# 8085_IO.net
KiCad netlist of a schematic drawn in EAGLE
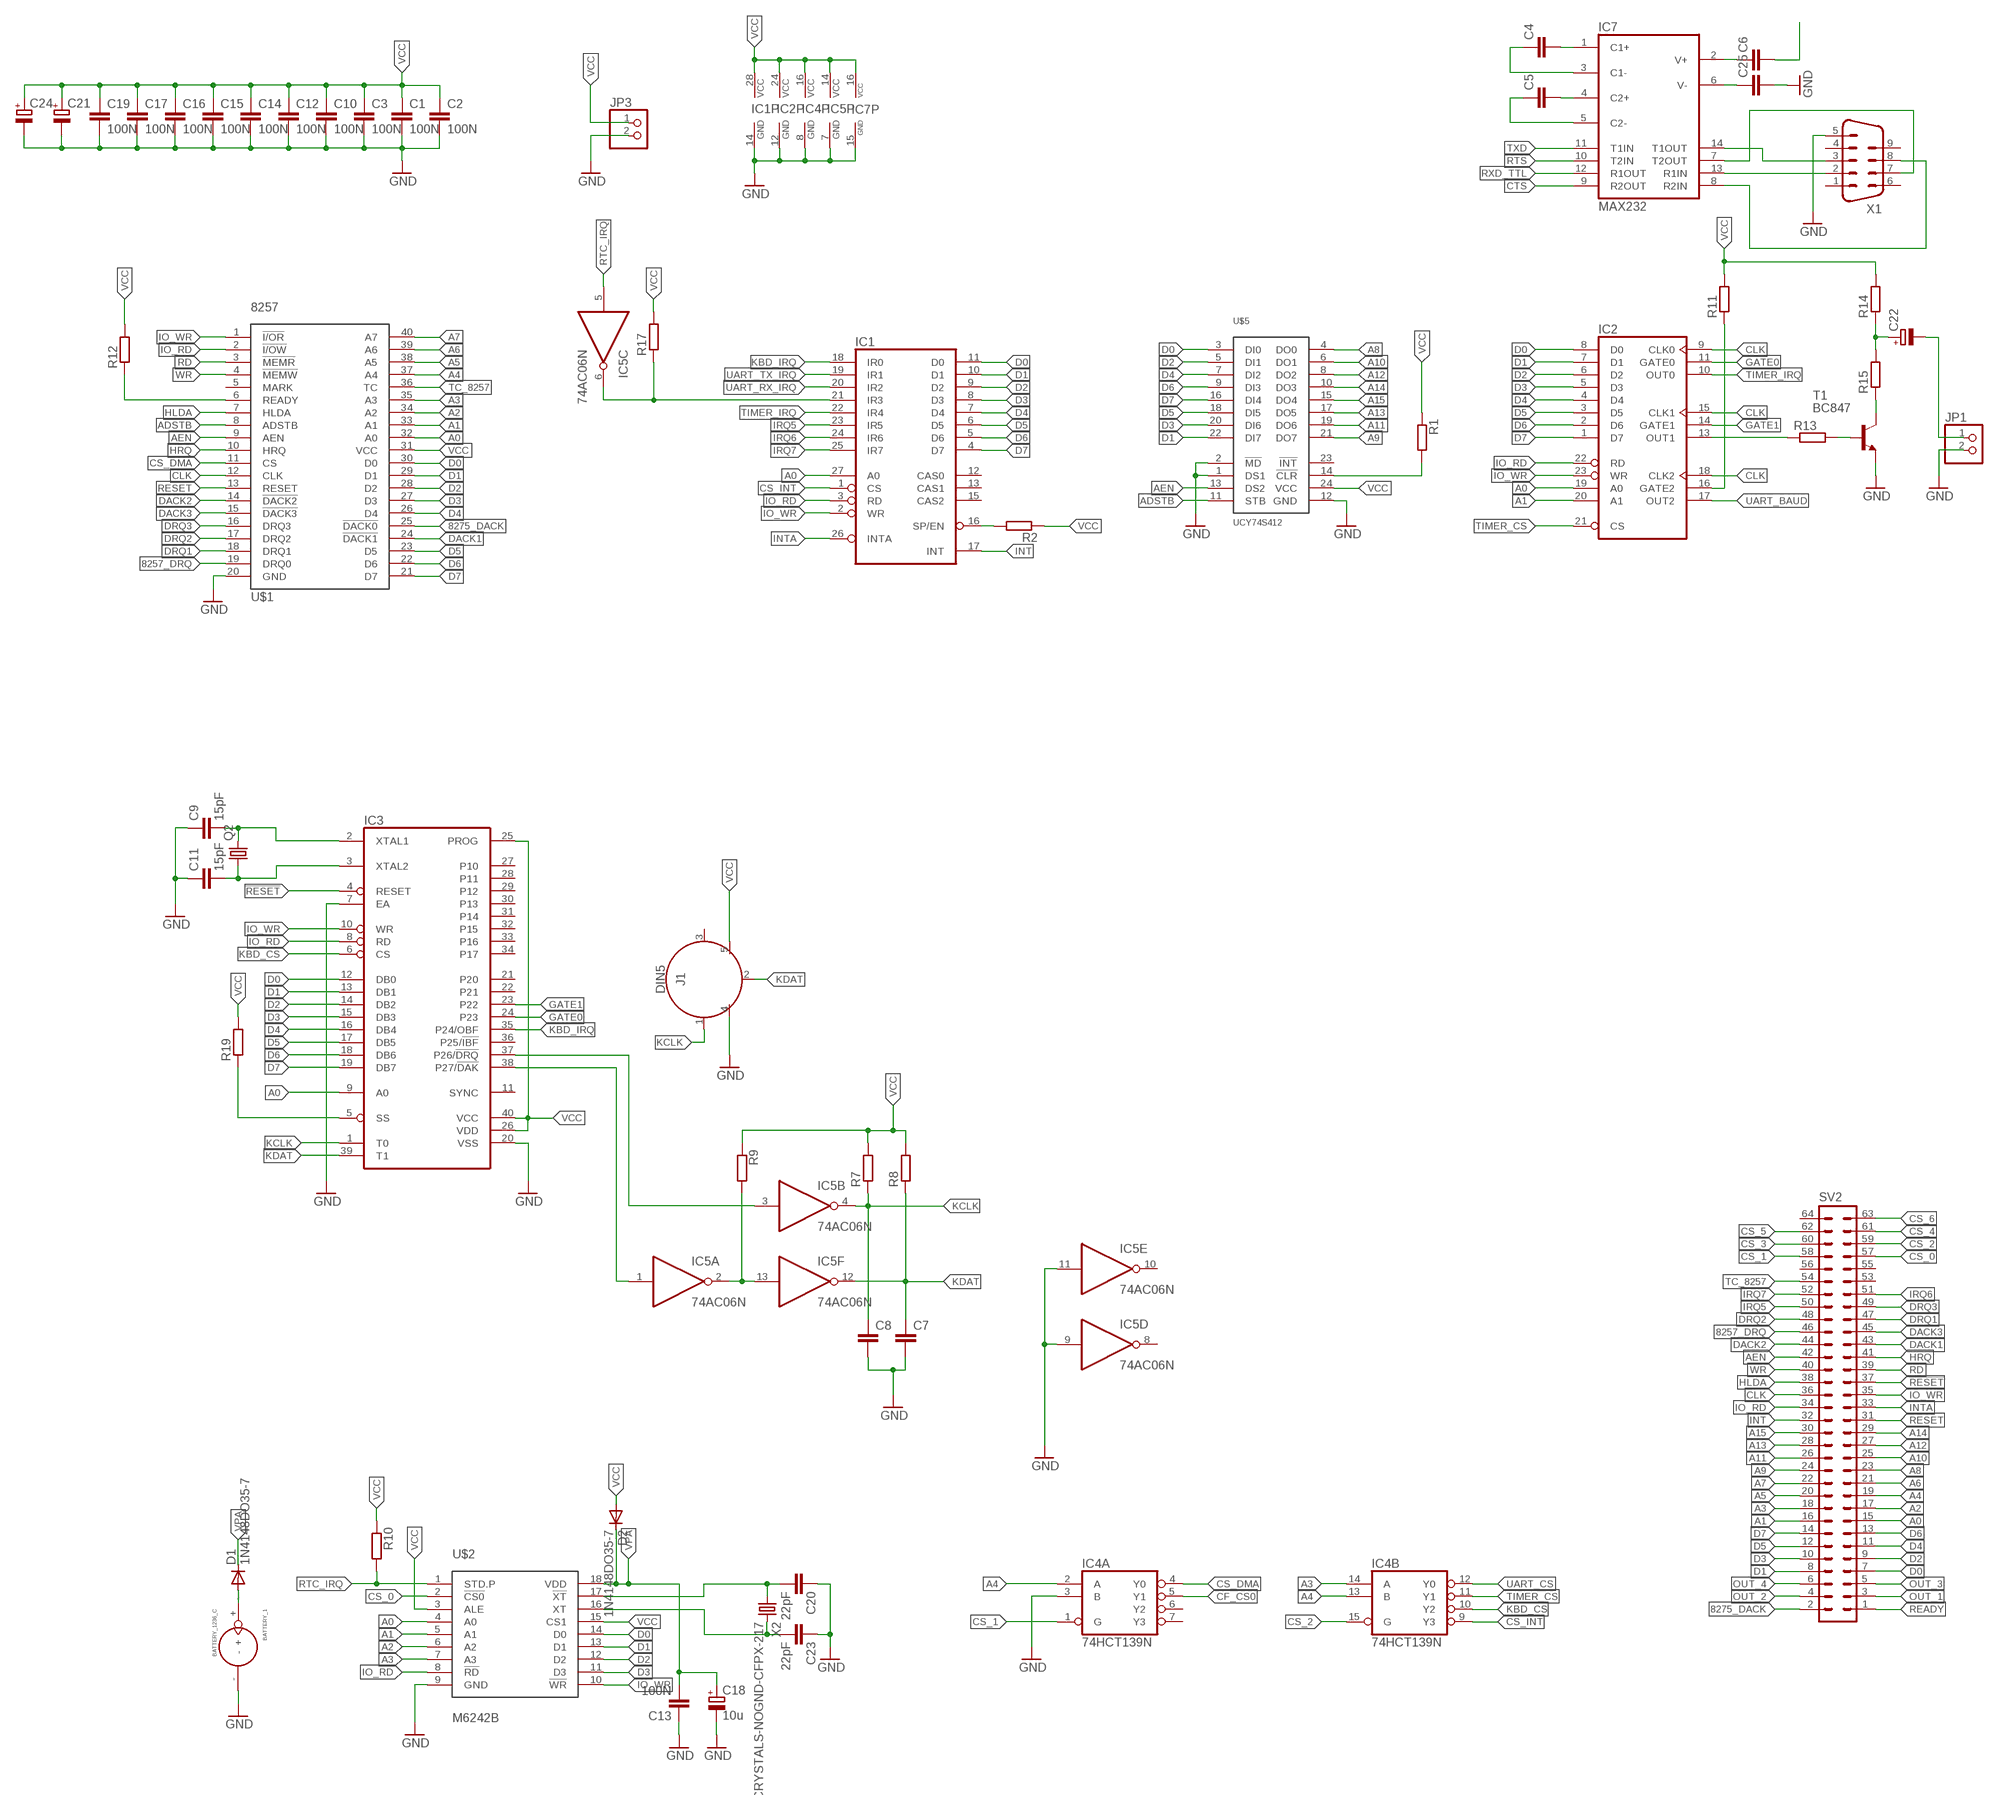
[diagram p0: schematic, sheet 1, part 1 of 2]
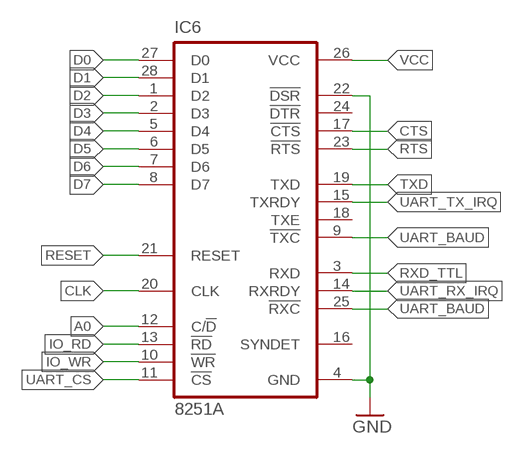
[diagram p1: schematic, sheet 1, part 2 of 2]

(export (version "E")
  (design (tool "Eeschema 10.0.6"))
  (components
    (comp (ref "BATTERY_1")
      (value "BATTERY_1236_C")
      (footprint "eagle-import:BATTERY_1236_C")
      (libsource (lib "eagle-import") (part "BATTERY_1236_C"))
    )
    (comp (ref "C1")
      (value "100N")
      (footprint "eagle-import:C0603")
      (libsource (lib "eagle-import") (part "C-EUC0603"))
    )
    (comp (ref "C2")
      (value "100N")
      (footprint "eagle-import:C1206")
      (libsource (lib "eagle-import") (part "C-EUC1206"))
    )
    (comp (ref "C3")
      (value "100N")
      (footprint "eagle-import:C0603")
      (libsource (lib "eagle-import") (part "C-EUC0603"))
    )
    (comp (ref "C4")
      (value "C-EUC0603")
      (footprint "eagle-import:C0603")
      (libsource (lib "eagle-import") (part "C-EUC0603"))
    )
    (comp (ref "C5")
      (value "C-EUC0603")
      (footprint "eagle-import:C0603")
      (libsource (lib "eagle-import") (part "C-EUC0603"))
    )
    (comp (ref "C6")
      (value "C-EUC0603")
      (footprint "eagle-import:C0603")
      (libsource (lib "eagle-import") (part "C-EUC0603"))
    )
    (comp (ref "C7")
      (value "C-EUC0603")
      (footprint "eagle-import:C0603")
      (libsource (lib "eagle-import") (part "C-EUC0603"))
    )
    (comp (ref "C8")
      (value "C-EUC0603")
      (footprint "eagle-import:C0603")
      (libsource (lib "eagle-import") (part "C-EUC0603"))
    )
    (comp (ref "C9")
      (value "15pF")
      (footprint "eagle-import:C0603")
      (libsource (lib "eagle-import") (part "C-EUC0603"))
    )
    (comp (ref "C10")
      (value "100N")
      (footprint "eagle-import:C0603")
      (libsource (lib "eagle-import") (part "C-EUC0603"))
    )
    (comp (ref "C11")
      (value "15pF")
      (footprint "eagle-import:C0603")
      (libsource (lib "eagle-import") (part "C-EUC0603"))
    )
    (comp (ref "C12")
      (value "100N")
      (footprint "eagle-import:C0603")
      (libsource (lib "eagle-import") (part "C-EUC0603"))
    )
    (comp (ref "C13")
      (value "100N")
      (footprint "eagle-import:C0603")
      (libsource (lib "eagle-import") (part "C-EUC0603"))
    )
    (comp (ref "C14")
      (value "100N")
      (footprint "eagle-import:C0603")
      (libsource (lib "eagle-import") (part "C-EUC0603"))
    )
    (comp (ref "C15")
      (value "100N")
      (footprint "eagle-import:C0603")
      (libsource (lib "eagle-import") (part "C-EUC0603"))
    )
    (comp (ref "C16")
      (value "100N")
      (footprint "eagle-import:C0603")
      (libsource (lib "eagle-import") (part "C-EUC0603"))
    )
    (comp (ref "C17")
      (value "100N")
      (footprint "eagle-import:C0603")
      (libsource (lib "eagle-import") (part "C-EUC0603"))
    )
    (comp (ref "C18")
      (value "10u")
      (footprint "eagle-import:SMC_B")
      (libsource (lib "eagle-import") (part "CPOL-EUSMCB"))
    )
    (comp (ref "C19")
      (value "100N")
      (footprint "eagle-import:C0603")
      (libsource (lib "eagle-import") (part "C-EUC0603"))
    )
    (comp (ref "C20")
      (value "22pF")
      (footprint "eagle-import:C0603")
      (libsource (lib "eagle-import") (part "C-EUC0603"))
    )
    (comp (ref "C21")
      (value "CPOL-EUE3.5-8")
      (footprint "eagle-import:E3,5-8")
      (libsource (lib "eagle-import") (part "CPOL-EUE3.5-8"))
    )
    (comp (ref "C22")
      (value "CPOL-EUE2-4")
      (footprint "eagle-import:E2-4")
      (libsource (lib "eagle-import") (part "CPOL-EUE2-4"))
    )
    (comp (ref "C23")
      (value "22pF")
      (footprint "eagle-import:C0603")
      (libsource (lib "eagle-import") (part "C-EUC0603"))
    )
    (comp (ref "C24")
      (value "CPOL-EUSMCB")
      (footprint "eagle-import:SMC_B")
      (libsource (lib "eagle-import") (part "CPOL-EUSMCB"))
    )
    (comp (ref "C25")
      (value "C-EUC0603")
      (footprint "eagle-import:C0603")
      (libsource (lib "eagle-import") (part "C-EUC0603"))
    )
    (comp (ref "D1")
      (value "1N4148DO35-7")
      (footprint "eagle-import:DO35-7")
      (libsource (lib "eagle-import") (part "1N4148DO35-7"))
    )
    (comp (ref "D2")
      (value "1N4148DO35-7")
      (footprint "eagle-import:DO35-7")
      (libsource (lib "eagle-import") (part "1N4148DO35-7"))
    )
    (comp (ref "IC1")
      (value "8259A")
      (footprint "eagle-import:DIL28-6")
      (libsource (lib "eagle-import") (part "8259A"))
    )
    (comp (ref "IC2")
      (value "8253")
      (footprint "eagle-import:DIL24-6")
      (libsource (lib "eagle-import") (part "8253"))
    )
    (comp (ref "IC3")
      (value "UPI-8042AH")
      (footprint "eagle-import:DIL40")
      (libsource (lib "eagle-import") (part "UPI-8042AH"))
    )
    (comp (ref "IC4")
      (value "74HCT139N")
      (footprint "eagle-import:DIL16")
      (libsource (lib "eagle-import") (part "74139NHCT"))
    )
    (comp (ref "IC5")
      (value "74AC06N")
      (footprint "eagle-import:DIL14")
      (libsource (lib "eagle-import") (part "7406NAC"))
    )
    (comp (ref "IC6")
      (value "8251A")
      (footprint "eagle-import:DIL28-6")
      (libsource (lib "eagle-import") (part "8251A"))
    )
    (comp (ref "IC7")
      (value "MAX232")
      (footprint "eagle-import:DIL16")
      (fields (field (name "MF") "MAXIM") (field (name "MPN") "MAX232ACPE+"))
      (libsource (lib "eagle-import") (part "MAX232"))
    )
    (comp (ref "J1")
      (value "DIN5")
      (footprint "eagle-import:DIN5-RA-PTH")
      (libsource (lib "eagle-import") (part "DIN5"))
    )
    (comp (ref "JP1")
      (value "PINHD-1X2")
      (footprint "eagle-import:1X02")
      (libsource (lib "eagle-import") (part "PINHD-1X2"))
    )
    (comp (ref "JP3")
      (value "PINHD-1X2/90")
      (footprint "eagle-import:1X02_90")
      (libsource (lib "eagle-import") (part "PINHD-1X2/90"))
    )
    (comp (ref "Q2")
      (value "CRYSTALHC49S")
      (footprint "eagle-import:HC49_S")
      (libsource (lib "eagle-import") (part "CRYSTALHC49S"))
    )
    (comp (ref "R1")
      (value "R-EU_R0603")
      (footprint "eagle-import:R0603")
      (libsource (lib "eagle-import") (part "R-EU_R0603"))
    )
    (comp (ref "R2")
      (value "R-EU_R0603")
      (footprint "eagle-import:R0603")
      (libsource (lib "eagle-import") (part "R-EU_R0603"))
    )
    (comp (ref "R7")
      (value "R-EU_0204/5")
      (footprint "eagle-import:0204_5")
      (libsource (lib "eagle-import") (part "R-EU_0204/5"))
    )
    (comp (ref "R8")
      (value "R-EU_M0805")
      (footprint "eagle-import:M0805")
      (libsource (lib "eagle-import") (part "R-EU_M0805"))
    )
    (comp (ref "R9")
      (value "R-EU_R0603")
      (footprint "eagle-import:R0603")
      (libsource (lib "eagle-import") (part "R-EU_R0603"))
    )
    (comp (ref "R10")
      (value "R-EU_R0603")
      (footprint "eagle-import:R0603")
      (libsource (lib "eagle-import") (part "R-EU_R0603"))
    )
    (comp (ref "R11")
      (value "R-EU_R0603")
      (footprint "eagle-import:R0603")
      (libsource (lib "eagle-import") (part "R-EU_R0603"))
    )
    (comp (ref "R12")
      (value "R-EU_R0603")
      (footprint "eagle-import:R0603")
      (libsource (lib "eagle-import") (part "R-EU_R0603"))
    )
    (comp (ref "R13")
      (value "R-EU_R0603")
      (footprint "eagle-import:R0603")
      (libsource (lib "eagle-import") (part "R-EU_R0603"))
    )
    (comp (ref "R14")
      (value "R-EU_0204/5")
      (footprint "eagle-import:0204_5")
      (libsource (lib "eagle-import") (part "R-EU_0204/5"))
    )
    (comp (ref "R15")
      (value "R-EU_R0603")
      (footprint "eagle-import:R0603")
      (libsource (lib "eagle-import") (part "R-EU_R0603"))
    )
    (comp (ref "R17")
      (value "R-EU_0204/7")
      (footprint "eagle-import:0204_7")
      (libsource (lib "eagle-import") (part "R-EU_0204/7"))
    )
    (comp (ref "R19")
      (value "R-EU_0204/5")
      (footprint "eagle-import:0204_5")
      (libsource (lib "eagle-import") (part "R-EU_0204/5"))
    )
    (comp (ref "SV2")
      (value "ML64L")
      (footprint "eagle-import:ML64L")
      (libsource (lib "eagle-import") (part "ML64L"))
    )
    (comp (ref "T1")
      (value "BC847")
      (footprint "eagle-import:SOT23")
      (libsource (lib "eagle-import") (part "BC847"))
    )
    (comp (ref "U$1")
      (value "8257")
      (footprint "eagle-import:DIL40")
      (libsource (lib "eagle-import") (part "8257"))
    )
    (comp (ref "U$2")
      (value "M6242B")
      (footprint "eagle-import:DIL18")
      (libsource (lib "eagle-import") (part "M6242B"))
    )
    (comp (ref "U$5")
      (value "UCY74S412")
      (footprint "eagle-import:DIL24-6")
      (libsource (lib "eagle-import") (part "UCY74S412"))
    )
    (comp (ref "X1")
      (value "M09HP")
      (footprint "eagle-import:M09HP")
      (libsource (lib "eagle-import") (part "M09HP"))
    )
    (comp (ref "X2")
      (value "CRYSTALS-NOGND-CFPX-217")
      (footprint "eagle-import:3.2X1.5-2-PAD")
      (libsource (lib "eagle-import") (part "CRYSTALS-NOGND-CFPX-217"))
    )
  )
  (nets
    (net (code "1") (name "/~{RESET}") (class "Default")
      (node (ref "IC3") (pin "4") (pinfunction "RESET_4") (pintype "input"))
      (node (ref "SV2") (pin "37") (pinfunction "37_37") (pintype "passive"))
    )
    (net (code "2") (name "8257_DRQ") (class "Default")
      (node (ref "SV2") (pin "46") (pinfunction "46_46") (pintype "passive"))
      (node (ref "U$1") (pin "19") (pinfunction "DRQ0_19") (pintype "bidirectional"))
    )
    (net (code "3") (name "8275_DACK") (class "Default")
      (node (ref "SV2") (pin "2") (pinfunction "2_2") (pintype "passive"))
      (node (ref "U$1") (pin "25") (pinfunction "~{DACK0}_25") (pintype "bidirectional"))
    )
    (net (code "4") (name "A0") (class "Default")
      (node (ref "IC1") (pin "27") (pinfunction "A0_27") (pintype "input"))
      (node (ref "IC2") (pin "19") (pinfunction "A0_19") (pintype "input"))
      (node (ref "IC3") (pin "9") (pinfunction "A0_9") (pintype "input"))
      (node (ref "IC6") (pin "12") (pinfunction "C/~{D}_12") (pintype "input"))
      (node (ref "SV2") (pin "15") (pinfunction "15_15") (pintype "passive"))
      (node (ref "U$1") (pin "32") (pinfunction "A0_32") (pintype "bidirectional"))
      (node (ref "U$2") (pin "4") (pinfunction "A0_4") (pintype "bidirectional"))
    )
    (net (code "5") (name "A1") (class "Default")
      (node (ref "IC2") (pin "20") (pinfunction "A1_20") (pintype "input"))
      (node (ref "SV2") (pin "16") (pinfunction "16_16") (pintype "passive"))
      (node (ref "U$1") (pin "33") (pinfunction "A1_33") (pintype "bidirectional"))
      (node (ref "U$2") (pin "5") (pinfunction "A1_5") (pintype "bidirectional"))
    )
    (net (code "6") (name "A2") (class "Default")
      (node (ref "SV2") (pin "17") (pinfunction "17_17") (pintype "passive"))
      (node (ref "U$1") (pin "34") (pinfunction "A2_34") (pintype "bidirectional"))
      (node (ref "U$2") (pin "6") (pinfunction "A2_6") (pintype "bidirectional"))
    )
    (net (code "7") (name "A3") (class "Default")
      (node (ref "IC4") (pin "14") (pinfunction "A_14") (pintype "input"))
      (node (ref "SV2") (pin "18") (pinfunction "18_18") (pintype "passive"))
      (node (ref "U$1") (pin "35") (pinfunction "A3_35") (pintype "bidirectional"))
      (node (ref "U$2") (pin "7") (pinfunction "A3_7") (pintype "bidirectional"))
    )
    (net (code "8") (name "A4") (class "Default")
      (node (ref "IC4") (pin "13") (pinfunction "B_13") (pintype "input"))
      (node (ref "IC4") (pin "2") (pinfunction "A_2") (pintype "input"))
      (node (ref "SV2") (pin "19") (pinfunction "19_19") (pintype "passive"))
      (node (ref "U$1") (pin "37") (pinfunction "A4_37") (pintype "bidirectional"))
    )
    (net (code "9") (name "A5") (class "Default")
      (node (ref "SV2") (pin "20") (pinfunction "20_20") (pintype "passive"))
      (node (ref "U$1") (pin "38") (pinfunction "A5_38") (pintype "bidirectional"))
    )
    (net (code "10") (name "A6") (class "Default")
      (node (ref "SV2") (pin "21") (pinfunction "21_21") (pintype "passive"))
      (node (ref "U$1") (pin "39") (pinfunction "A6_39") (pintype "bidirectional"))
    )
    (net (code "11") (name "A7") (class "Default")
      (node (ref "SV2") (pin "22") (pinfunction "22_22") (pintype "passive"))
      (node (ref "U$1") (pin "40") (pinfunction "A7_40") (pintype "bidirectional"))
    )
    (net (code "12") (name "A8") (class "Default")
      (node (ref "SV2") (pin "23") (pinfunction "23_23") (pintype "passive"))
      (node (ref "U$5") (pin "4") (pinfunction "DO0_4") (pintype "bidirectional"))
    )
    (net (code "13") (name "A9") (class "Default")
      (node (ref "SV2") (pin "24") (pinfunction "24_24") (pintype "passive"))
      (node (ref "U$5") (pin "21") (pinfunction "DO7_21") (pintype "bidirectional"))
    )
    (net (code "14") (name "A10") (class "Default")
      (node (ref "SV2") (pin "25") (pinfunction "25_25") (pintype "passive"))
      (node (ref "U$5") (pin "6") (pinfunction "DO1_6") (pintype "bidirectional"))
    )
    (net (code "15") (name "A11") (class "Default")
      (node (ref "SV2") (pin "26") (pinfunction "26_26") (pintype "passive"))
      (node (ref "U$5") (pin "19") (pinfunction "DO6_19") (pintype "bidirectional"))
    )
    (net (code "16") (name "A12") (class "Default")
      (node (ref "SV2") (pin "27") (pinfunction "27_27") (pintype "passive"))
      (node (ref "U$5") (pin "8") (pinfunction "DO2_8") (pintype "bidirectional"))
    )
    (net (code "17") (name "A13") (class "Default")
      (node (ref "SV2") (pin "28") (pinfunction "28_28") (pintype "passive"))
      (node (ref "U$5") (pin "17") (pinfunction "DO5_17") (pintype "bidirectional"))
    )
    (net (code "18") (name "A14") (class "Default")
      (node (ref "SV2") (pin "29") (pinfunction "29_29") (pintype "passive"))
      (node (ref "U$5") (pin "10") (pinfunction "DO3_10") (pintype "bidirectional"))
    )
    (net (code "19") (name "A15") (class "Default")
      (node (ref "SV2") (pin "30") (pinfunction "30_30") (pintype "passive"))
      (node (ref "U$5") (pin "15") (pinfunction "DO4_15") (pintype "bidirectional"))
    )
    (net (code "20") (name "ADSTB") (class "Default")
      (node (ref "U$1") (pin "8") (pinfunction "ADSTB_8") (pintype "bidirectional"))
      (node (ref "U$5") (pin "11") (pinfunction "STB_11") (pintype "bidirectional"))
    )
    (net (code "21") (name "AEN") (class "Default")
      (node (ref "SV2") (pin "42") (pinfunction "42_42") (pintype "passive"))
      (node (ref "U$1") (pin "9") (pinfunction "AEN_9") (pintype "bidirectional"))
      (node (ref "U$5") (pin "13") (pinfunction "DS2_13") (pintype "bidirectional"))
    )
    (net (code "22") (name "CF_CS0") (class "Default")
      (node (ref "IC4") (pin "5") (pinfunction "Y1_5") (pintype "output"))
    )
    (net (code "23") (name "CLK") (class "Default")
      (node (ref "IC2") (pin "15") (pinfunction "CLK1_15") (pintype "input"))
      (node (ref "IC2") (pin "18") (pinfunction "CLK2_18") (pintype "input"))
      (node (ref "IC2") (pin "9") (pinfunction "CLK0_9") (pintype "input"))
      (node (ref "IC6") (pin "20") (pinfunction "CLK_20") (pintype "input"))
      (node (ref "SV2") (pin "36") (pinfunction "36_36") (pintype "passive"))
      (node (ref "U$1") (pin "12") (pinfunction "CLK_12") (pintype "bidirectional"))
    )
    (net (code "24") (name "CS_0") (class "Default")
      (node (ref "SV2") (pin "57") (pinfunction "57_57") (pintype "passive"))
      (node (ref "U$2") (pin "2") (pinfunction "~{CS0}_2") (pintype "bidirectional"))
    )
    (net (code "25") (name "CS_1") (class "Default")
      (node (ref "IC4") (pin "1") (pinfunction "G_1") (pintype "input"))
      (node (ref "SV2") (pin "58") (pinfunction "58_58") (pintype "passive"))
    )
    (net (code "26") (name "CS_2") (class "Default")
      (node (ref "IC4") (pin "15") (pinfunction "G_15") (pintype "input"))
      (node (ref "SV2") (pin "59") (pinfunction "59_59") (pintype "passive"))
    )
    (net (code "27") (name "CS_3") (class "Default")
      (node (ref "SV2") (pin "60") (pinfunction "60_60") (pintype "passive"))
    )
    (net (code "28") (name "CS_4") (class "Default")
      (node (ref "SV2") (pin "61") (pinfunction "61_61") (pintype "passive"))
    )
    (net (code "29") (name "CS_5") (class "Default")
      (node (ref "SV2") (pin "62") (pinfunction "62_62") (pintype "passive"))
    )
    (net (code "30") (name "CS_6") (class "Default")
      (node (ref "SV2") (pin "63") (pinfunction "63_63") (pintype "passive"))
    )
    (net (code "31") (name "CS_DMA") (class "Default")
      (node (ref "IC4") (pin "4") (pinfunction "Y0_4") (pintype "output"))
      (node (ref "U$1") (pin "11") (pinfunction "CS_11") (pintype "bidirectional"))
    )
    (net (code "32") (name "CS_INT") (class "Default")
      (node (ref "IC1") (pin "1") (pinfunction "CS_1") (pintype "input"))
      (node (ref "IC4") (pin "9") (pinfunction "Y3_9") (pintype "output"))
    )
    (net (code "33") (name "CTS") (class "Default")
      (node (ref "IC6") (pin "17") (pinfunction "~{CTS}_17") (pintype "input"))
      (node (ref "IC7") (pin "9") (pinfunction "R2OUT_9") (pintype "output"))
    )
    (net (code "34") (name "D0") (class "Default")
      (node (ref "IC1") (pin "11") (pinfunction "D0_11") (pintype "bidirectional"))
      (node (ref "IC2") (pin "8") (pinfunction "D0_8") (pintype "bidirectional"))
      (node (ref "IC3") (pin "12") (pinfunction "DB0_12") (pintype "bidirectional"))
      (node (ref "IC6") (pin "27") (pinfunction "D0_27") (pintype "tri_state"))
      (node (ref "SV2") (pin "7") (pinfunction "7_7") (pintype "passive"))
      (node (ref "U$1") (pin "30") (pinfunction "D0_30") (pintype "bidirectional"))
      (node (ref "U$2") (pin "14") (pinfunction "D0_14") (pintype "bidirectional"))
      (node (ref "U$5") (pin "3") (pinfunction "DI0_3") (pintype "bidirectional"))
    )
    (net (code "35") (name "D1") (class "Default")
      (node (ref "IC1") (pin "10") (pinfunction "D1_10") (pintype "bidirectional"))
      (node (ref "IC2") (pin "7") (pinfunction "D1_7") (pintype "bidirectional"))
      (node (ref "IC3") (pin "13") (pinfunction "DB1_13") (pintype "bidirectional"))
      (node (ref "IC6") (pin "28") (pinfunction "D1_28") (pintype "tri_state"))
      (node (ref "SV2") (pin "8") (pinfunction "8_8") (pintype "passive"))
      (node (ref "U$1") (pin "29") (pinfunction "D1_29") (pintype "bidirectional"))
      (node (ref "U$2") (pin "13") (pinfunction "D1_13") (pintype "bidirectional"))
      (node (ref "U$5") (pin "22") (pinfunction "DI7_22") (pintype "bidirectional"))
    )
    (net (code "36") (name "D2") (class "Default")
      (node (ref "IC1") (pin "9") (pinfunction "D2_9") (pintype "bidirectional"))
      (node (ref "IC2") (pin "6") (pinfunction "D2_6") (pintype "bidirectional"))
      (node (ref "IC3") (pin "14") (pinfunction "DB2_14") (pintype "bidirectional"))
      (node (ref "IC6") (pin "1") (pinfunction "D2_1") (pintype "tri_state"))
      (node (ref "SV2") (pin "9") (pinfunction "9_9") (pintype "passive"))
      (node (ref "U$1") (pin "28") (pinfunction "D2_28") (pintype "bidirectional"))
      (node (ref "U$2") (pin "12") (pinfunction "D2_12") (pintype "bidirectional"))
      (node (ref "U$5") (pin "5") (pinfunction "DI1_5") (pintype "bidirectional"))
    )
    (net (code "37") (name "D3") (class "Default")
      (node (ref "IC1") (pin "8") (pinfunction "D3_8") (pintype "bidirectional"))
      (node (ref "IC2") (pin "5") (pinfunction "D3_5") (pintype "bidirectional"))
      (node (ref "IC3") (pin "15") (pinfunction "DB3_15") (pintype "bidirectional"))
      (node (ref "IC6") (pin "2") (pinfunction "D3_2") (pintype "tri_state"))
      (node (ref "SV2") (pin "10") (pinfunction "10_10") (pintype "passive"))
      (node (ref "U$1") (pin "27") (pinfunction "D3_27") (pintype "bidirectional"))
      (node (ref "U$2") (pin "11") (pinfunction "D3_11") (pintype "bidirectional"))
      (node (ref "U$5") (pin "20") (pinfunction "DI6_20") (pintype "bidirectional"))
    )
    (net (code "38") (name "D4") (class "Default")
      (node (ref "IC1") (pin "7") (pinfunction "D4_7") (pintype "bidirectional"))
      (node (ref "IC2") (pin "4") (pinfunction "D4_4") (pintype "bidirectional"))
      (node (ref "IC3") (pin "16") (pinfunction "DB4_16") (pintype "bidirectional"))
      (node (ref "IC6") (pin "5") (pinfunction "D4_5") (pintype "tri_state"))
      (node (ref "SV2") (pin "11") (pinfunction "11_11") (pintype "passive"))
      (node (ref "U$1") (pin "26") (pinfunction "D4_26") (pintype "bidirectional"))
      (node (ref "U$5") (pin "7") (pinfunction "DI2_7") (pintype "bidirectional"))
    )
    (net (code "39") (name "D5") (class "Default")
      (node (ref "IC1") (pin "6") (pinfunction "D5_6") (pintype "bidirectional"))
      (node (ref "IC2") (pin "3") (pinfunction "D5_3") (pintype "bidirectional"))
      (node (ref "IC3") (pin "17") (pinfunction "DB5_17") (pintype "bidirectional"))
      (node (ref "IC6") (pin "6") (pinfunction "D5_6") (pintype "tri_state"))
      (node (ref "SV2") (pin "12") (pinfunction "12_12") (pintype "passive"))
      (node (ref "U$1") (pin "23") (pinfunction "D5_23") (pintype "bidirectional"))
      (node (ref "U$5") (pin "18") (pinfunction "DI5_18") (pintype "bidirectional"))
    )
    (net (code "40") (name "D6") (class "Default")
      (node (ref "IC1") (pin "5") (pinfunction "D6_5") (pintype "bidirectional"))
      (node (ref "IC2") (pin "2") (pinfunction "D6_2") (pintype "bidirectional"))
      (node (ref "IC3") (pin "18") (pinfunction "DB6_18") (pintype "bidirectional"))
      (node (ref "IC6") (pin "7") (pinfunction "D6_7") (pintype "tri_state"))
      (node (ref "SV2") (pin "13") (pinfunction "13_13") (pintype "passive"))
      (node (ref "U$1") (pin "22") (pinfunction "D6_22") (pintype "bidirectional"))
      (node (ref "U$5") (pin "9") (pinfunction "DI3_9") (pintype "bidirectional"))
    )
    (net (code "41") (name "D7") (class "Default")
      (node (ref "IC1") (pin "4") (pinfunction "D7_4") (pintype "bidirectional"))
      (node (ref "IC2") (pin "1") (pinfunction "D7_1") (pintype "bidirectional"))
      (node (ref "IC3") (pin "19") (pinfunction "DB7_19") (pintype "bidirectional"))
      (node (ref "IC6") (pin "8") (pinfunction "D7_8") (pintype "tri_state"))
      (node (ref "SV2") (pin "14") (pinfunction "14_14") (pintype "passive"))
      (node (ref "U$1") (pin "21") (pinfunction "D7_21") (pintype "bidirectional"))
      (node (ref "U$5") (pin "16") (pinfunction "DI4_16") (pintype "bidirectional"))
    )
    (net (code "42") (name "DACK1") (class "Default")
      (node (ref "SV2") (pin "43") (pinfunction "43_43") (pintype "passive"))
      (node (ref "U$1") (pin "24") (pinfunction "~{DACK1}_24") (pintype "bidirectional"))
    )
    (net (code "43") (name "DACK2") (class "Default")
      (node (ref "SV2") (pin "44") (pinfunction "44_44") (pintype "passive"))
      (node (ref "U$1") (pin "14") (pinfunction "~{DACK2}_14") (pintype "bidirectional"))
    )
    (net (code "44") (name "DACK3") (class "Default")
      (node (ref "SV2") (pin "45") (pinfunction "45_45") (pintype "passive"))
      (node (ref "U$1") (pin "15") (pinfunction "~{DACK3}_15") (pintype "bidirectional"))
    )
    (net (code "45") (name "DRQ1") (class "Default")
      (node (ref "SV2") (pin "47") (pinfunction "47_47") (pintype "passive"))
      (node (ref "U$1") (pin "18") (pinfunction "DRQ1_18") (pintype "bidirectional"))
    )
    (net (code "46") (name "DRQ2") (class "Default")
      (node (ref "SV2") (pin "48") (pinfunction "48_48") (pintype "passive"))
      (node (ref "U$1") (pin "17") (pinfunction "DRQ2_17") (pintype "bidirectional"))
    )
    (net (code "47") (name "DRQ3") (class "Default")
      (node (ref "SV2") (pin "49") (pinfunction "49_49") (pintype "passive"))
      (node (ref "U$1") (pin "16") (pinfunction "DRQ3_16") (pintype "bidirectional"))
    )
    (net (code "48") (name "GATE0") (class "Default")
      (node (ref "IC2") (pin "11") (pinfunction "GATE0_11") (pintype "input"))
      (node (ref "IC3") (pin "24") (pinfunction "P23_24") (pintype "bidirectional"))
    )
    (net (code "49") (name "GATE1") (class "Default")
      (node (ref "IC2") (pin "14") (pinfunction "GATE1_14") (pintype "input"))
      (node (ref "IC3") (pin "23") (pinfunction "P22_23") (pintype "bidirectional"))
    )
    (net (code "50") (name "GND") (class "Default")
      (node (ref "BATTERY_1") (pin "-") (pinfunction "-_-") (pintype "bidirectional"))
      (node (ref "C1") (pin "2") (pinfunction "2_2") (pintype "passive"))
      (node (ref "C10") (pin "2") (pinfunction "2_2") (pintype "passive"))
      (node (ref "C11") (pin "1") (pinfunction "1_1") (pintype "passive"))
      (node (ref "C12") (pin "2") (pinfunction "2_2") (pintype "passive"))
      (node (ref "C13") (pin "1") (pinfunction "1_1") (pintype "passive"))
      (node (ref "C14") (pin "2") (pinfunction "2_2") (pintype "passive"))
      (node (ref "C15") (pin "2") (pinfunction "2_2") (pintype "passive"))
      (node (ref "C16") (pin "2") (pinfunction "2_2") (pintype "passive"))
      (node (ref "C17") (pin "2") (pinfunction "2_2") (pintype "passive"))
      (node (ref "C18") (pin "-") (pinfunction "-_-") (pintype "passive"))
      (node (ref "C19") (pin "2") (pinfunction "2_2") (pintype "passive"))
      (node (ref "C2") (pin "2") (pinfunction "2_2") (pintype "passive"))
      (node (ref "C20") (pin "1") (pinfunction "1_1") (pintype "passive"))
      (node (ref "C21") (pin "-") (pinfunction "-_-") (pintype "passive"))
      (node (ref "C23") (pin "1") (pinfunction "1_1") (pintype "passive"))
      (node (ref "C24") (pin "-") (pinfunction "-_-") (pintype "passive"))
      (node (ref "C25") (pin "2") (pinfunction "2_2") (pintype "passive"))
      (node (ref "C3") (pin "2") (pinfunction "2_2") (pintype "passive"))
      (node (ref "C7") (pin "2") (pinfunction "2_2") (pintype "passive"))
      (node (ref "C8") (pin "2") (pinfunction "2_2") (pintype "passive"))
      (node (ref "C9") (pin "1") (pinfunction "1_1") (pintype "passive"))
      (node (ref "IC1") (pin "14") (pinfunction "GND_14") (pintype "power_in"))
      (node (ref "IC2") (pin "12") (pinfunction "GND_12") (pintype "power_in"))
      (node (ref "IC3") (pin "20") (pinfunction "VSS_20") (pintype "power_in"))
      (node (ref "IC3") (pin "7") (pinfunction "EA_7") (pintype "input"))
      (node (ref "IC4") (pin "3") (pinfunction "B_3") (pintype "input"))
      (node (ref "IC4") (pin "8") (pinfunction "GND_8") (pintype "power_in"))
      (node (ref "IC5") (pin "11") (pinfunction "I_11") (pintype "input"))
      (node (ref "IC5") (pin "7") (pinfunction "GND_7") (pintype "power_in"))
      (node (ref "IC5") (pin "9") (pinfunction "I_9") (pintype "input"))
      (node (ref "IC6") (pin "22") (pinfunction "~{DSR}_22") (pintype "input"))
      (node (ref "IC6") (pin "4") (pinfunction "GND_4") (pintype "power_in"))
      (node (ref "IC7") (pin "15") (pinfunction "GND_15") (pintype "power_in"))
      (node (ref "J1") (pin "4") (pinfunction "4_4") (pintype "bidirectional"))
      (node (ref "JP1") (pin "2") (pinfunction "2_2") (pintype "passive"))
      (node (ref "JP3") (pin "2") (pinfunction "2_2") (pintype "passive"))
      (node (ref "T1") (pin "2") (pinfunction "E_2") (pintype "passive"))
      (node (ref "U$1") (pin "20") (pinfunction "GND_20") (pintype "bidirectional"))
      (node (ref "U$2") (pin "9") (pinfunction "GND_9") (pintype "bidirectional"))
      (node (ref "U$5") (pin "1") (pinfunction "DS1_1") (pintype "bidirectional"))
      (node (ref "U$5") (pin "12") (pinfunction "GND_12") (pintype "bidirectional"))
      (node (ref "U$5") (pin "2") (pinfunction "~{MD}_2") (pintype "bidirectional"))
      (node (ref "X1") (pin "5") (pinfunction "5_5") (pintype "passive"))
    )
    (net (code "51") (name "HLDA") (class "Default")
      (node (ref "SV2") (pin "38") (pinfunction "38_38") (pintype "passive"))
      (node (ref "U$1") (pin "7") (pinfunction "HLDA_7") (pintype "bidirectional"))
    )
    (net (code "52") (name "HRQ") (class "Default")
      (node (ref "SV2") (pin "41") (pinfunction "41_41") (pintype "passive"))
      (node (ref "U$1") (pin "10") (pinfunction "HRQ_10") (pintype "bidirectional"))
    )
    (net (code "53") (name "INT") (class "Default")
      (node (ref "IC1") (pin "17") (pinfunction "INT_17") (pintype "output"))
      (node (ref "SV2") (pin "32") (pinfunction "32_32") (pintype "passive"))
    )
    (net (code "54") (name "INTA") (class "Default")
      (node (ref "IC1") (pin "26") (pinfunction "INTA_26") (pintype "input"))
      (node (ref "SV2") (pin "33") (pinfunction "33_33") (pintype "passive"))
    )
    (net (code "55") (name "IO_RD") (class "Default")
      (node (ref "IC1") (pin "3") (pinfunction "RD_3") (pintype "input"))
      (node (ref "IC2") (pin "22") (pinfunction "RD_22") (pintype "input"))
      (node (ref "IC3") (pin "8") (pinfunction "RD_8") (pintype "input"))
      (node (ref "IC6") (pin "13") (pinfunction "~{RD}_13") (pintype "input"))
      (node (ref "SV2") (pin "34") (pinfunction "34_34") (pintype "passive"))
      (node (ref "U$1") (pin "2") (pinfunction "~{I/OW}_2") (pintype "bidirectional"))
      (node (ref "U$2") (pin "8") (pinfunction "~{RD}_8") (pintype "bidirectional"))
    )
    (net (code "56") (name "IO_WR") (class "Default")
      (node (ref "IC1") (pin "2") (pinfunction "WR_2") (pintype "input"))
      (node (ref "IC2") (pin "23") (pinfunction "WR_23") (pintype "input"))
      (node (ref "IC3") (pin "10") (pinfunction "WR_10") (pintype "input"))
      (node (ref "IC6") (pin "10") (pinfunction "~{WR}_10") (pintype "input"))
      (node (ref "SV2") (pin "35") (pinfunction "35_35") (pintype "passive"))
      (node (ref "U$1") (pin "1") (pinfunction "~{I/OR}_1") (pintype "bidirectional"))
      (node (ref "U$2") (pin "10") (pinfunction "~{WR}_10") (pintype "bidirectional"))
    )
    (net (code "57") (name "IRQ5") (class "Default")
      (node (ref "IC1") (pin "23") (pinfunction "IR5_23") (pintype "input"))
      (node (ref "SV2") (pin "50") (pinfunction "50_50") (pintype "passive"))
    )
    (net (code "58") (name "IRQ6") (class "Default")
      (node (ref "IC1") (pin "24") (pinfunction "IR6_24") (pintype "input"))
      (node (ref "SV2") (pin "51") (pinfunction "51_51") (pintype "passive"))
    )
    (net (code "59") (name "IRQ7") (class "Default")
      (node (ref "IC1") (pin "25") (pinfunction "IR7_25") (pintype "input"))
      (node (ref "SV2") (pin "52") (pinfunction "52_52") (pintype "passive"))
    )
    (net (code "60") (name "KBD_CS") (class "Default")
      (node (ref "IC3") (pin "6") (pinfunction "CS_6") (pintype "input"))
      (node (ref "IC4") (pin "10") (pinfunction "Y2_10") (pintype "output"))
    )
    (net (code "61") (name "KBD_IRQ") (class "Default")
      (node (ref "IC1") (pin "18") (pinfunction "IR0_18") (pintype "input"))
      (node (ref "IC3") (pin "35") (pinfunction "P24/OBF_35") (pintype "bidirectional"))
    )
    (net (code "62") (name "KCLK") (class "Default")
      (node (ref "C8") (pin "1") (pinfunction "1_1") (pintype "passive"))
      (node (ref "IC3") (pin "1") (pinfunction "T0_1") (pintype "input"))
      (node (ref "IC5") (pin "4") (pinfunction "O_4") (pintype "open_collector"))
      (node (ref "J1") (pin "1") (pinfunction "1_1") (pintype "bidirectional"))
      (node (ref "R7") (pin "1") (pinfunction "1_1") (pintype "passive"))
    )
    (net (code "63") (name "KDAT") (class "Default")
      (node (ref "C7") (pin "1") (pinfunction "1_1") (pintype "passive"))
      (node (ref "IC3") (pin "39") (pinfunction "T1_39") (pintype "input"))
      (node (ref "IC5") (pin "12") (pinfunction "O_12") (pintype "open_collector"))
      (node (ref "J1") (pin "2") (pinfunction "2_2") (pintype "bidirectional"))
      (node (ref "R8") (pin "1") (pinfunction "1_1") (pintype "passive"))
    )
    (net (code "64") (name "Net-(BATTERY_1-Pad+)") (class "Default")
      (node (ref "BATTERY_1") (pin "+") (pinfunction "+_+") (pintype "bidirectional"))
      (node (ref "D1") (pin "A") (pinfunction "A_A") (pintype "passive"))
    )
    (net (code "65") (name "Net-(C22-Pad+)") (class "Default")
      (node (ref "C22") (pin "+") (pinfunction "+_+") (pintype "passive"))
      (node (ref "R14") (pin "1") (pinfunction "1_1") (pintype "passive"))
      (node (ref "R15") (pin "2") (pinfunction "2_2") (pintype "passive"))
    )
    (net (code "66") (name "Net-(C22-Pad-)") (class "Default")
      (node (ref "C22") (pin "-") (pinfunction "-_-") (pintype "passive"))
      (node (ref "JP1") (pin "1") (pinfunction "1_1") (pintype "passive"))
    )
    (net (code "67") (name "Net-(IC1A-IR3)") (class "Default")
      (node (ref "IC1") (pin "21") (pinfunction "IR3_21") (pintype "input"))
      (node (ref "IC5") (pin "6") (pinfunction "O_6") (pintype "open_collector"))
      (node (ref "R17") (pin "1") (pinfunction "1_1") (pintype "passive"))
    )
    (net (code "68") (name "Net-(IC1A-SP{slash}EN)") (class "Default")
      (node (ref "IC1") (pin "16") (pinfunction "SP/EN_16") (pintype "bidirectional"))
      (node (ref "R2") (pin "2") (pinfunction "2_2") (pintype "passive"))
    )
    (net (code "69") (name "Net-(IC2A-GATE2)") (class "Default")
      (node (ref "IC2") (pin "16") (pinfunction "GATE2_16") (pintype "input"))
      (node (ref "R11") (pin "1") (pinfunction "1_1") (pintype "passive"))
    )
    (net (code "70") (name "Net-(IC2A-OUT1)") (class "Default")
      (node (ref "IC2") (pin "13") (pinfunction "OUT1_13") (pintype "output"))
      (node (ref "R13") (pin "1") (pinfunction "1_1") (pintype "passive"))
    )
    (net (code "71") (name "Net-(IC3-P26{slash}~{DRQ})") (class "Default")
      (node (ref "IC3") (pin "37") (pinfunction "P26/~{DRQ}_37") (pintype "bidirectional"))
      (node (ref "IC5") (pin "3") (pinfunction "I_3") (pintype "input"))
    )
    (net (code "72") (name "Net-(IC3-P27{slash}~{DAK})") (class "Default")
      (node (ref "IC3") (pin "38") (pinfunction "P27/~{DAK}_38") (pintype "bidirectional"))
      (node (ref "IC5") (pin "1") (pinfunction "I_1") (pintype "input"))
    )
    (net (code "73") (name "Net-(IC3-SS)") (class "Default")
      (node (ref "IC3") (pin "5") (pinfunction "SS_5") (pintype "input"))
      (node (ref "R19") (pin "1") (pinfunction "1_1") (pintype "passive"))
    )
    (net (code "74") (name "Net-(IC3-XTAL1)") (class "Default")
      (node (ref "C9") (pin "2") (pinfunction "2_2") (pintype "passive"))
      (node (ref "IC3") (pin "2") (pinfunction "XTAL1_2") (pintype "input"))
      (node (ref "Q2") (pin "2") (pinfunction "2_2") (pintype "passive"))
    )
    (net (code "75") (name "Net-(IC3-XTAL2)") (class "Default")
      (node (ref "C11") (pin "2") (pinfunction "2_2") (pintype "passive"))
      (node (ref "IC3") (pin "3") (pinfunction "XTAL2_3") (pintype "input"))
      (node (ref "Q2") (pin "1") (pinfunction "1_1") (pintype "passive"))
    )
    (net (code "76") (name "Net-(IC5A-O)") (class "Default")
      (node (ref "IC5") (pin "13") (pinfunction "I_13") (pintype "input"))
      (node (ref "IC5") (pin "2") (pinfunction "O_2") (pintype "open_collector"))
      (node (ref "R9") (pin "2") (pinfunction "2_2") (pintype "passive"))
    )
    (net (code "77") (name "Net-(IC7A-C1+)") (class "Default")
      (node (ref "C4") (pin "2") (pinfunction "2_2") (pintype "passive"))
      (node (ref "IC7") (pin "1") (pinfunction "C1+_1") (pintype "bidirectional"))
    )
    (net (code "78") (name "Net-(IC7A-C1-)") (class "Default")
      (node (ref "C4") (pin "1") (pinfunction "1_1") (pintype "passive"))
      (node (ref "IC7") (pin "3") (pinfunction "C1-_3") (pintype "bidirectional"))
    )
    (net (code "79") (name "Net-(IC7A-C2+)") (class "Default")
      (node (ref "C5") (pin "2") (pinfunction "2_2") (pintype "passive"))
      (node (ref "IC7") (pin "4") (pinfunction "C2+_4") (pintype "bidirectional"))
    )
    (net (code "80") (name "Net-(IC7A-C2-)") (class "Default")
      (node (ref "C5") (pin "1") (pinfunction "1_1") (pintype "passive"))
      (node (ref "IC7") (pin "5") (pinfunction "C2-_5") (pintype "bidirectional"))
    )
    (net (code "81") (name "Net-(IC7A-R1IN)") (class "Default")
      (node (ref "IC7") (pin "13") (pinfunction "R1IN_13") (pintype "input"))
      (node (ref "X1") (pin "2") (pinfunction "2_2") (pintype "passive"))
    )
    (net (code "82") (name "Net-(IC7A-R2IN)") (class "Default")
      (node (ref "IC7") (pin "8") (pinfunction "R2IN_8") (pintype "input"))
      (node (ref "X1") (pin "8") (pinfunction "8_8") (pintype "passive"))
    )
    (net (code "83") (name "Net-(IC7A-T1OUT)") (class "Default")
      (node (ref "IC7") (pin "14") (pinfunction "T1OUT_14") (pintype "output"))
      (node (ref "X1") (pin "3") (pinfunction "3_3") (pintype "passive"))
    )
    (net (code "84") (name "Net-(IC7A-T2OUT)") (class "Default")
      (node (ref "IC7") (pin "7") (pinfunction "T2OUT_7") (pintype "output"))
      (node (ref "X1") (pin "7") (pinfunction "7_7") (pintype "passive"))
    )
    (net (code "85") (name "Net-(IC7A-V+)") (class "Default")
      (node (ref "C6") (pin "1") (pinfunction "1_1") (pintype "passive"))
      (node (ref "IC7") (pin "2") (pinfunction "V+_2") (pintype "bidirectional"))
    )
    (net (code "86") (name "Net-(IC7A-V-)") (class "Default")
      (node (ref "C25") (pin "1") (pinfunction "1_1") (pintype "passive"))
      (node (ref "IC7") (pin "6") (pinfunction "V-_6") (pintype "bidirectional"))
    )
    (net (code "87") (name "Net-(T1-B)") (class "Default")
      (node (ref "R13") (pin "2") (pinfunction "2_2") (pintype "passive"))
      (node (ref "T1") (pin "1") (pinfunction "B_1") (pintype "passive"))
    )
    (net (code "88") (name "Net-(T1-C)") (class "Default")
      (node (ref "R15") (pin "1") (pinfunction "1_1") (pintype "passive"))
      (node (ref "T1") (pin "3") (pinfunction "C_3") (pintype "passive"))
    )
    (net (code "89") (name "Net-(U$1-READY)") (class "Default")
      (node (ref "R12") (pin "1") (pinfunction "1_1") (pintype "passive"))
      (node (ref "U$1") (pin "6") (pinfunction "READY_6") (pintype "bidirectional"))
    )
    (net (code "90") (name "Net-(U$2-XT)") (class "Default")
      (node (ref "C23") (pin "2") (pinfunction "2_2") (pintype "passive"))
      (node (ref "U$2") (pin "16") (pinfunction "XT_16") (pintype "bidirectional"))
      (node (ref "X2") (pin "2") (pinfunction "2_2") (pintype "passive"))
    )
    (net (code "91") (name "Net-(U$2-~{XT})") (class "Default")
      (node (ref "C20") (pin "2") (pinfunction "2_2") (pintype "passive"))
      (node (ref "U$2") (pin "17") (pinfunction "~{XT}_17") (pintype "bidirectional"))
      (node (ref "X2") (pin "1") (pinfunction "1_1") (pintype "passive"))
    )
    (net (code "92") (name "Net-(U$5-~{CLR})") (class "Default")
      (node (ref "R1") (pin "2") (pinfunction "2_2") (pintype "passive"))
      (node (ref "U$5") (pin "14") (pinfunction "~{CLR}_14") (pintype "bidirectional"))
    )
    (net (code "93") (name "OUT_1") (class "Default")
      (node (ref "SV2") (pin "3") (pinfunction "3_3") (pintype "passive"))
    )
    (net (code "94") (name "OUT_2") (class "Default")
      (node (ref "SV2") (pin "4") (pinfunction "4_4") (pintype "passive"))
    )
    (net (code "95") (name "OUT_3") (class "Default")
      (node (ref "SV2") (pin "5") (pinfunction "5_5") (pintype "passive"))
    )
    (net (code "96") (name "OUT_4") (class "Default")
      (node (ref "SV2") (pin "6") (pinfunction "6_6") (pintype "passive"))
    )
    (net (code "97") (name "RD") (class "Default")
      (node (ref "SV2") (pin "39") (pinfunction "39_39") (pintype "passive"))
      (node (ref "U$1") (pin "3") (pinfunction "~{MEMR}_3") (pintype "bidirectional"))
    )
    (net (code "98") (name "READY") (class "Default")
      (node (ref "SV2") (pin "1") (pinfunction "1_1") (pintype "passive"))
    )
    (net (code "99") (name "RESET") (class "Default")
      (node (ref "IC6") (pin "21") (pinfunction "RESET_21") (pintype "input"))
      (node (ref "SV2") (pin "31") (pinfunction "31_31") (pintype "passive"))
      (node (ref "U$1") (pin "13") (pinfunction "RESET_13") (pintype "bidirectional"))
    )
    (net (code "100") (name "RTC_IRQ") (class "Default")
      (node (ref "IC5") (pin "5") (pinfunction "I_5") (pintype "input"))
      (node (ref "R10") (pin "2") (pinfunction "2_2") (pintype "passive"))
      (node (ref "U$2") (pin "1") (pinfunction "STD.P_1") (pintype "bidirectional"))
    )
    (net (code "101") (name "RTS") (class "Default")
      (node (ref "IC6") (pin "23") (pinfunction "~{RTS}_23") (pintype "output"))
      (node (ref "IC7") (pin "10") (pinfunction "T2IN_10") (pintype "input"))
    )
    (net (code "102") (name "RXD_TTL") (class "Default")
      (node (ref "IC6") (pin "3") (pinfunction "RXD_3") (pintype "input"))
      (node (ref "IC7") (pin "12") (pinfunction "R1OUT_12") (pintype "output"))
    )
    (net (code "103") (name "TC_8257") (class "Default")
      (node (ref "SV2") (pin "54") (pinfunction "54_54") (pintype "passive"))
      (node (ref "U$1") (pin "36") (pinfunction "TC_36") (pintype "bidirectional"))
    )
    (net (code "104") (name "TIMER_CS") (class "Default")
      (node (ref "IC2") (pin "21") (pinfunction "CS_21") (pintype "input"))
      (node (ref "IC4") (pin "11") (pinfunction "Y1_11") (pintype "output"))
    )
    (net (code "105") (name "TIMER_IRQ") (class "Default")
      (node (ref "IC1") (pin "22") (pinfunction "IR4_22") (pintype "input"))
      (node (ref "IC2") (pin "10") (pinfunction "OUT0_10") (pintype "output"))
    )
    (net (code "106") (name "TXD") (class "Default")
      (node (ref "IC6") (pin "19") (pinfunction "TXD_19") (pintype "output"))
      (node (ref "IC7") (pin "11") (pinfunction "T1IN_11") (pintype "input"))
    )
    (net (code "107") (name "UART_BAUD") (class "Default")
      (node (ref "IC2") (pin "17") (pinfunction "OUT2_17") (pintype "output"))
      (node (ref "IC6") (pin "25") (pinfunction "~{RXC}_25") (pintype "input"))
      (node (ref "IC6") (pin "9") (pinfunction "~{TXC}_9") (pintype "input"))
    )
    (net (code "108") (name "UART_CS") (class "Default")
      (node (ref "IC4") (pin "12") (pinfunction "Y0_12") (pintype "output"))
      (node (ref "IC6") (pin "11") (pinfunction "~{CS}_11") (pintype "input"))
    )
    (net (code "109") (name "UART_RX_IRQ") (class "Default")
      (node (ref "IC1") (pin "20") (pinfunction "IR2_20") (pintype "input"))
      (node (ref "IC6") (pin "14") (pinfunction "RXRDY_14") (pintype "output"))
    )
    (net (code "110") (name "UART_TX_IRQ") (class "Default")
      (node (ref "IC1") (pin "19") (pinfunction "IR1_19") (pintype "input"))
      (node (ref "IC6") (pin "15") (pinfunction "TXRDY_15") (pintype "output"))
    )
    (net (code "111") (name "VCC") (class "Default")
      (node (ref "C1") (pin "1") (pinfunction "1_1") (pintype "passive"))
      (node (ref "C10") (pin "1") (pinfunction "1_1") (pintype "passive"))
      (node (ref "C12") (pin "1") (pinfunction "1_1") (pintype "passive"))
      (node (ref "C14") (pin "1") (pinfunction "1_1") (pintype "passive"))
      (node (ref "C15") (pin "1") (pinfunction "1_1") (pintype "passive"))
      (node (ref "C16") (pin "1") (pinfunction "1_1") (pintype "passive"))
      (node (ref "C17") (pin "1") (pinfunction "1_1") (pintype "passive"))
      (node (ref "C19") (pin "1") (pinfunction "1_1") (pintype "passive"))
      (node (ref "C2") (pin "1") (pinfunction "1_1") (pintype "passive"))
      (node (ref "C21") (pin "+") (pinfunction "+_+") (pintype "passive"))
      (node (ref "C24") (pin "+") (pinfunction "+_+") (pintype "passive"))
      (node (ref "C3") (pin "1") (pinfunction "1_1") (pintype "passive"))
      (node (ref "C6") (pin "2") (pinfunction "2_2") (pintype "passive"))
      (node (ref "D2") (pin "A") (pinfunction "A_A") (pintype "passive"))
      (node (ref "IC1") (pin "28") (pinfunction "VCC_28") (pintype "power_in"))
      (node (ref "IC2") (pin "24") (pinfunction "VCC_24") (pintype "power_in"))
      (node (ref "IC3") (pin "25") (pinfunction "PROG_25") (pintype "bidirectional"))
      (node (ref "IC3") (pin "26") (pinfunction "VDD_26") (pintype "power_in"))
      (node (ref "IC3") (pin "40") (pinfunction "VCC_40") (pintype "power_in"))
      (node (ref "IC4") (pin "16") (pinfunction "VCC_16") (pintype "power_in"))
      (node (ref "IC5") (pin "14") (pinfunction "VCC_14") (pintype "power_in"))
      (node (ref "IC6") (pin "26") (pinfunction "VCC_26") (pintype "power_in"))
      (node (ref "IC7") (pin "16") (pinfunction "VCC_16") (pintype "power_in"))
      (node (ref "J1") (pin "5") (pinfunction "5_5") (pintype "bidirectional"))
      (node (ref "JP3") (pin "1") (pinfunction "1_1") (pintype "passive"))
      (node (ref "R1") (pin "1") (pinfunction "1_1") (pintype "passive"))
      (node (ref "R10") (pin "1") (pinfunction "1_1") (pintype "passive"))
      (node (ref "R11") (pin "2") (pinfunction "2_2") (pintype "passive"))
      (node (ref "R12") (pin "2") (pinfunction "2_2") (pintype "passive"))
      (node (ref "R14") (pin "2") (pinfunction "2_2") (pintype "passive"))
      (node (ref "R17") (pin "2") (pinfunction "2_2") (pintype "passive"))
      (node (ref "R19") (pin "2") (pinfunction "2_2") (pintype "passive"))
      (node (ref "R2") (pin "1") (pinfunction "1_1") (pintype "passive"))
      (node (ref "R7") (pin "2") (pinfunction "2_2") (pintype "passive"))
      (node (ref "R8") (pin "2") (pinfunction "2_2") (pintype "passive"))
      (node (ref "R9") (pin "1") (pinfunction "1_1") (pintype "passive"))
      (node (ref "U$1") (pin "31") (pinfunction "VCC_31") (pintype "bidirectional"))
      (node (ref "U$2") (pin "15") (pinfunction "CS1_15") (pintype "bidirectional"))
      (node (ref "U$2") (pin "3") (pinfunction "ALE_3") (pintype "bidirectional"))
      (node (ref "U$5") (pin "24") (pinfunction "VCC_24") (pintype "bidirectional"))
    )
    (net (code "112") (name "VPA") (class "Default")
      (node (ref "C13") (pin "2") (pinfunction "2_2") (pintype "passive"))
      (node (ref "C18") (pin "+") (pinfunction "+_+") (pintype "passive"))
      (node (ref "D1") (pin "C") (pinfunction "C_C") (pintype "passive"))
      (node (ref "D2") (pin "C") (pinfunction "C_C") (pintype "passive"))
      (node (ref "U$2") (pin "18") (pinfunction "VDD_18") (pintype "bidirectional"))
    )
    (net (code "113") (name "WR") (class "Default")
      (node (ref "SV2") (pin "40") (pinfunction "40_40") (pintype "passive"))
      (node (ref "U$1") (pin "4") (pinfunction "~{MEMW}_4") (pintype "bidirectional"))
    )
    (net (code "114") (name "unconnected-(IC1A-CAS0-Pad12)") (class "Default")
      (node (ref "IC1") (pin "12") (pinfunction "CAS0_12") (pintype "bidirectional"))
    )
    (net (code "115") (name "unconnected-(IC1A-CAS1-Pad13)") (class "Default")
      (node (ref "IC1") (pin "13") (pinfunction "CAS1_13") (pintype "bidirectional"))
    )
    (net (code "116") (name "unconnected-(IC1A-CAS2-Pad15)") (class "Default")
      (node (ref "IC1") (pin "15") (pinfunction "CAS2_15") (pintype "bidirectional"))
    )
    (net (code "117") (name "unconnected-(IC3-P10-Pad27)") (class "Default")
      (node (ref "IC3") (pin "27") (pinfunction "P10_27") (pintype "bidirectional"))
    )
    (net (code "118") (name "unconnected-(IC3-P11-Pad28)") (class "Default")
      (node (ref "IC3") (pin "28") (pinfunction "P11_28") (pintype "bidirectional"))
    )
    (net (code "119") (name "unconnected-(IC3-P12-Pad29)") (class "Default")
      (node (ref "IC3") (pin "29") (pinfunction "P12_29") (pintype "bidirectional"))
    )
    (net (code "120") (name "unconnected-(IC3-P13-Pad30)") (class "Default")
      (node (ref "IC3") (pin "30") (pinfunction "P13_30") (pintype "bidirectional"))
    )
    (net (code "121") (name "unconnected-(IC3-P14-Pad31)") (class "Default")
      (node (ref "IC3") (pin "31") (pinfunction "P14_31") (pintype "bidirectional"))
    )
    (net (code "122") (name "unconnected-(IC3-P15-Pad32)") (class "Default")
      (node (ref "IC3") (pin "32") (pinfunction "P15_32") (pintype "bidirectional"))
    )
    (net (code "123") (name "unconnected-(IC3-P16-Pad33)") (class "Default")
      (node (ref "IC3") (pin "33") (pinfunction "P16_33") (pintype "bidirectional"))
    )
    (net (code "124") (name "unconnected-(IC3-P17-Pad34)") (class "Default")
      (node (ref "IC3") (pin "34") (pinfunction "P17_34") (pintype "bidirectional"))
    )
    (net (code "125") (name "unconnected-(IC3-P20-Pad21)") (class "Default")
      (node (ref "IC3") (pin "21") (pinfunction "P20_21") (pintype "bidirectional"))
    )
    (net (code "126") (name "unconnected-(IC3-P21-Pad22)") (class "Default")
      (node (ref "IC3") (pin "22") (pinfunction "P21_22") (pintype "bidirectional"))
    )
    (net (code "127") (name "unconnected-(IC3-P25{slash}~{IBF}-Pad36)") (class "Default")
      (node (ref "IC3") (pin "36") (pinfunction "P25/~{IBF}_36") (pintype "bidirectional"))
    )
    (net (code "128") (name "unconnected-(IC3-SYNC-Pad11)") (class "Default")
      (node (ref "IC3") (pin "11") (pinfunction "SYNC_11") (pintype "output"))
    )
    (net (code "129") (name "unconnected-(IC4A-Y2-Pad6)") (class "Default")
      (node (ref "IC4") (pin "6") (pinfunction "Y2_6") (pintype "output"))
    )
    (net (code "130") (name "unconnected-(IC4A-Y3-Pad7)") (class "Default")
      (node (ref "IC4") (pin "7") (pinfunction "Y3_7") (pintype "output"))
    )
    (net (code "131") (name "unconnected-(IC5D-O-Pad8)") (class "Default")
      (node (ref "IC5") (pin "8") (pinfunction "O_8") (pintype "open_collector"))
    )
    (net (code "132") (name "unconnected-(IC5E-O-Pad10)") (class "Default")
      (node (ref "IC5") (pin "10") (pinfunction "O_10") (pintype "open_collector"))
    )
    (net (code "133") (name "unconnected-(IC6-SYNDET-Pad16)") (class "Default")
      (node (ref "IC6") (pin "16") (pinfunction "SYNDET_16") (pintype "bidirectional"))
    )
    (net (code "134") (name "unconnected-(IC6-TXE-Pad18)") (class "Default")
      (node (ref "IC6") (pin "18") (pinfunction "TXE_18") (pintype "output"))
    )
    (net (code "135") (name "unconnected-(IC6-~{DTR}-Pad24)") (class "Default")
      (node (ref "IC6") (pin "24") (pinfunction "~{DTR}_24") (pintype "output"))
    )
    (net (code "136") (name "unconnected-(J1-Pad3)") (class "Default")
      (node (ref "J1") (pin "3") (pinfunction "3_3") (pintype "bidirectional"))
    )
    (net (code "137") (name "unconnected-(SV2-Pad53)") (class "Default")
      (node (ref "SV2") (pin "53") (pinfunction "53_53") (pintype "passive"))
    )
    (net (code "138") (name "unconnected-(SV2-Pad55)") (class "Default")
      (node (ref "SV2") (pin "55") (pinfunction "55_55") (pintype "passive"))
    )
    (net (code "139") (name "unconnected-(SV2-Pad56)") (class "Default")
      (node (ref "SV2") (pin "56") (pinfunction "56_56") (pintype "passive"))
    )
    (net (code "140") (name "unconnected-(SV2-Pad64)") (class "Default")
      (node (ref "SV2") (pin "64") (pinfunction "64_64") (pintype "passive"))
    )
    (net (code "141") (name "unconnected-(U$1-MARK-Pad5)") (class "Default")
      (node (ref "U$1") (pin "5") (pinfunction "MARK_5") (pintype "bidirectional"))
    )
    (net (code "142") (name "unconnected-(U$5-~{INT}-Pad23)") (class "Default")
      (node (ref "U$5") (pin "23") (pinfunction "~{INT}_23") (pintype "bidirectional"))
    )
    (net (code "143") (name "unconnected-(X1-Pad1)") (class "Default")
      (node (ref "X1") (pin "1") (pinfunction "1_1") (pintype "passive"))
    )
    (net (code "144") (name "unconnected-(X1-Pad4)") (class "Default")
      (node (ref "X1") (pin "4") (pinfunction "4_4") (pintype "passive"))
    )
    (net (code "145") (name "unconnected-(X1-Pad6)") (class "Default")
      (node (ref "X1") (pin "6") (pinfunction "6_6") (pintype "passive"))
    )
    (net (code "146") (name "unconnected-(X1-Pad9)") (class "Default")
      (node (ref "X1") (pin "9") (pinfunction "9_9") (pintype "passive"))
    )
  )
)
